# MotorDriver.net
KiCad netlist of a schematic drawn in EAGLE
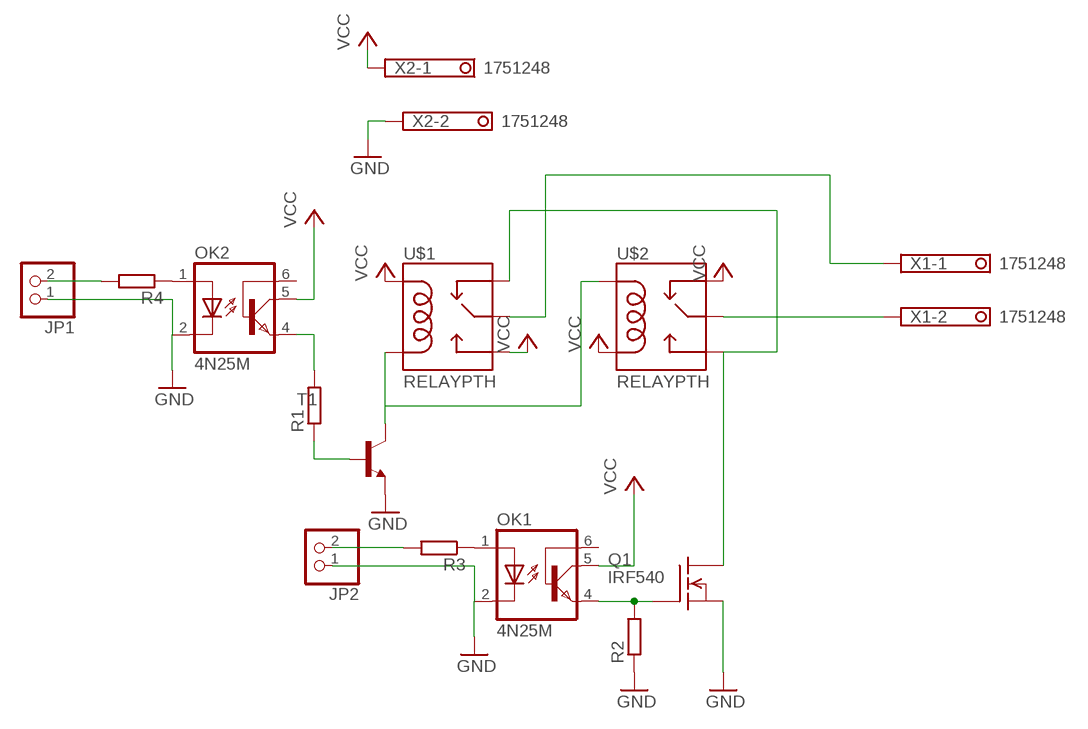
[diagram p0: schematic, sheet 1]

(export (version "E")
  (design (tool "Eeschema 10.0.6"))
  (components
    (comp (ref "JP1")
      (value "PINHD-1X2")
      (footprint "eagle-import:1X02")
      (libsource (lib "eagle-import") (part "PINHD-1X2"))
    )
    (comp (ref "JP2")
      (value "PINHD-1X2")
      (footprint "eagle-import:1X02")
      (libsource (lib "eagle-import") (part "PINHD-1X2"))
    )
    (comp (ref "OK1")
      (value "4N25M")
      (footprint "eagle-import:DIL06")
      (fields (field (name "MPN") "4N25-M"))
      (libsource (lib "eagle-import") (part "4N?M25"))
    )
    (comp (ref "OK2")
      (value "4N25M")
      (footprint "eagle-import:DIL06")
      (fields (field (name "MPN") "4N25-M"))
      (libsource (lib "eagle-import") (part "4N?M25"))
    )
    (comp (ref "Q1")
      (value "IRF540")
      (footprint "eagle-import:TO220")
      (libsource (lib "eagle-import") (part "IRF540"))
    )
    (comp (ref "R1")
      (value "R-EU_0204/7")
      (footprint "eagle-import:0204_7")
      (libsource (lib "eagle-import") (part "R-EU_0204/7"))
    )
    (comp (ref "R2")
      (value "R-EU_0204/7")
      (footprint "eagle-import:0204_7")
      (libsource (lib "eagle-import") (part "R-EU_0204/7"))
    )
    (comp (ref "R3")
      (value "R-EU_0204/7")
      (footprint "eagle-import:0204_7")
      (libsource (lib "eagle-import") (part "R-EU_0204/7"))
    )
    (comp (ref "R4")
      (value "R-EU_0204/7")
      (footprint "eagle-import:0204_7")
      (libsource (lib "eagle-import") (part "R-EU_0204/7"))
    )
    (comp (ref "T1")
      (value "2N2222-NPN-TO92-EBC")
      (footprint "eagle-import:TO92-EBC")
      (libsource (lib "eagle-import") (part "-NPN-TO92-EBC2N2222"))
    )
    (comp (ref "U$1")
      (value "RELAYPTH")
      (footprint "eagle-import:SRD-05VDC-SL-C")
      (libsource (lib "eagle-import") (part "RELAYPTH"))
    )
    (comp (ref "U$2")
      (value "RELAYPTH")
      (footprint "eagle-import:SRD-05VDC-SL-C")
      (libsource (lib "eagle-import") (part "RELAYPTH"))
    )
    (comp (ref "X1")
      (value "1751248")
      (footprint "eagle-import:1751248")
      (libsource (lib "eagle-import") (part "1751248"))
    )
    (comp (ref "X2")
      (value "1751248")
      (footprint "eagle-import:1751248")
      (libsource (lib "eagle-import") (part "1751248"))
    )
  )
  (nets
    (net (code "1") (name "GND") (class "Default")
      (node (ref "JP1") (pin "1") (pinfunction "1_1") (pintype "passive"))
      (node (ref "JP2") (pin "1") (pinfunction "1_1") (pintype "passive"))
      (node (ref "OK1") (pin "2") (pinfunction "C_2") (pintype "passive"))
      (node (ref "OK2") (pin "2") (pinfunction "C_2") (pintype "passive"))
      (node (ref "Q1") (pin "3") (pinfunction "S_3") (pintype "passive"))
      (node (ref "R2") (pin "1") (pinfunction "1_1") (pintype "passive"))
      (node (ref "T1") (pin "E") (pinfunction "E_E") (pintype "passive"))
      (node (ref "X2") (pin "2") (pinfunction "K_2") (pintype "passive"))
    )
    (net (code "2") (name "Net-(JP1-Pad2)") (class "Default")
      (node (ref "JP1") (pin "2") (pinfunction "2_2") (pintype "passive"))
      (node (ref "R4") (pin "2") (pinfunction "2_2") (pintype "passive"))
    )
    (net (code "3") (name "Net-(JP2-Pad2)") (class "Default")
      (node (ref "JP2") (pin "2") (pinfunction "2_2") (pintype "passive"))
      (node (ref "R3") (pin "2") (pinfunction "2_2") (pintype "passive"))
    )
    (net (code "4") (name "Net-(OK1-A)") (class "Default")
      (node (ref "OK1") (pin "1") (pinfunction "A_1") (pintype "passive"))
      (node (ref "R3") (pin "1") (pinfunction "1_1") (pintype "passive"))
    )
    (net (code "5") (name "Net-(OK1-EMI)") (class "Default")
      (node (ref "OK1") (pin "4") (pinfunction "EMI_4") (pintype "passive"))
      (node (ref "Q1") (pin "1") (pinfunction "G_1") (pintype "passive"))
      (node (ref "R2") (pin "2") (pinfunction "2_2") (pintype "passive"))
    )
    (net (code "6") (name "Net-(OK2-A)") (class "Default")
      (node (ref "OK2") (pin "1") (pinfunction "A_1") (pintype "passive"))
      (node (ref "R4") (pin "1") (pinfunction "1_1") (pintype "passive"))
    )
    (net (code "7") (name "Net-(OK2-EMI)") (class "Default")
      (node (ref "OK2") (pin "4") (pinfunction "EMI_4") (pintype "passive"))
      (node (ref "R1") (pin "2") (pinfunction "2_2") (pintype "passive"))
    )
    (net (code "8") (name "Net-(Q1-D)") (class "Default")
      (node (ref "Q1") (pin "2") (pinfunction "D_2") (pintype "passive"))
      (node (ref "U$1") (pin "SWCLOSED") (pinfunction "SWCLOSE_SWCLOSED") (pintype "bidirectional"))
      (node (ref "U$2") (pin "SWOPEN") (pinfunction "SWOPEN_SWOPEN") (pintype "bidirectional"))
    )
    (net (code "9") (name "Net-(R1-Pad1)") (class "Default")
      (node (ref "R1") (pin "1") (pinfunction "1_1") (pintype "passive"))
      (node (ref "T1") (pin "B") (pinfunction "B_B") (pintype "passive"))
    )
    (net (code "10") (name "Net-(T1-PadC)") (class "Default")
      (node (ref "T1") (pin "C") (pinfunction "C_C") (pintype "passive"))
      (node (ref "U$1") (pin "COIL0") (pinfunction "COIL0_COIL0") (pintype "bidirectional"))
      (node (ref "U$2") (pin "COIL1") (pinfunction "COIL1_COIL1") (pintype "bidirectional"))
    )
    (net (code "11") (name "Net-(X1A-K)") (class "Default")
      (node (ref "U$1") (pin "SWCOMMON") (pinfunction "SWCOMMON_SWCOMMON") (pintype "bidirectional"))
      (node (ref "X1") (pin "1") (pinfunction "K_1") (pintype "passive"))
    )
    (net (code "12") (name "Net-(X1B-K)") (class "Default")
      (node (ref "U$2") (pin "SWCOMMON") (pinfunction "SWCOMMON_SWCOMMON") (pintype "bidirectional"))
      (node (ref "X1") (pin "2") (pinfunction "K_2") (pintype "passive"))
    )
    (net (code "13") (name "VCC") (class "Default")
      (node (ref "OK1") (pin "5") (pinfunction "COL_5") (pintype "passive"))
      (node (ref "OK2") (pin "5") (pinfunction "COL_5") (pintype "passive"))
      (node (ref "U$1") (pin "COIL1") (pinfunction "COIL1_COIL1") (pintype "bidirectional"))
      (node (ref "U$1") (pin "SWOPEN") (pinfunction "SWOPEN_SWOPEN") (pintype "bidirectional"))
      (node (ref "U$2") (pin "COIL0") (pinfunction "COIL0_COIL0") (pintype "bidirectional"))
      (node (ref "U$2") (pin "SWCLOSED") (pinfunction "SWCLOSE_SWCLOSED") (pintype "bidirectional"))
      (node (ref "X2") (pin "1") (pinfunction "K_1") (pintype "passive"))
    )
    (net (code "14") (name "unconnected-(OK1-BAS-Pad6)") (class "Default")
      (node (ref "OK1") (pin "6") (pinfunction "BAS_6") (pintype "passive"))
    )
    (net (code "15") (name "unconnected-(OK2-BAS-Pad6)") (class "Default")
      (node (ref "OK2") (pin "6") (pinfunction "BAS_6") (pintype "passive"))
    )
  )
)
